# Schema_FoxDigi.net
KiCad netlist of a schematic drawn in EAGLE
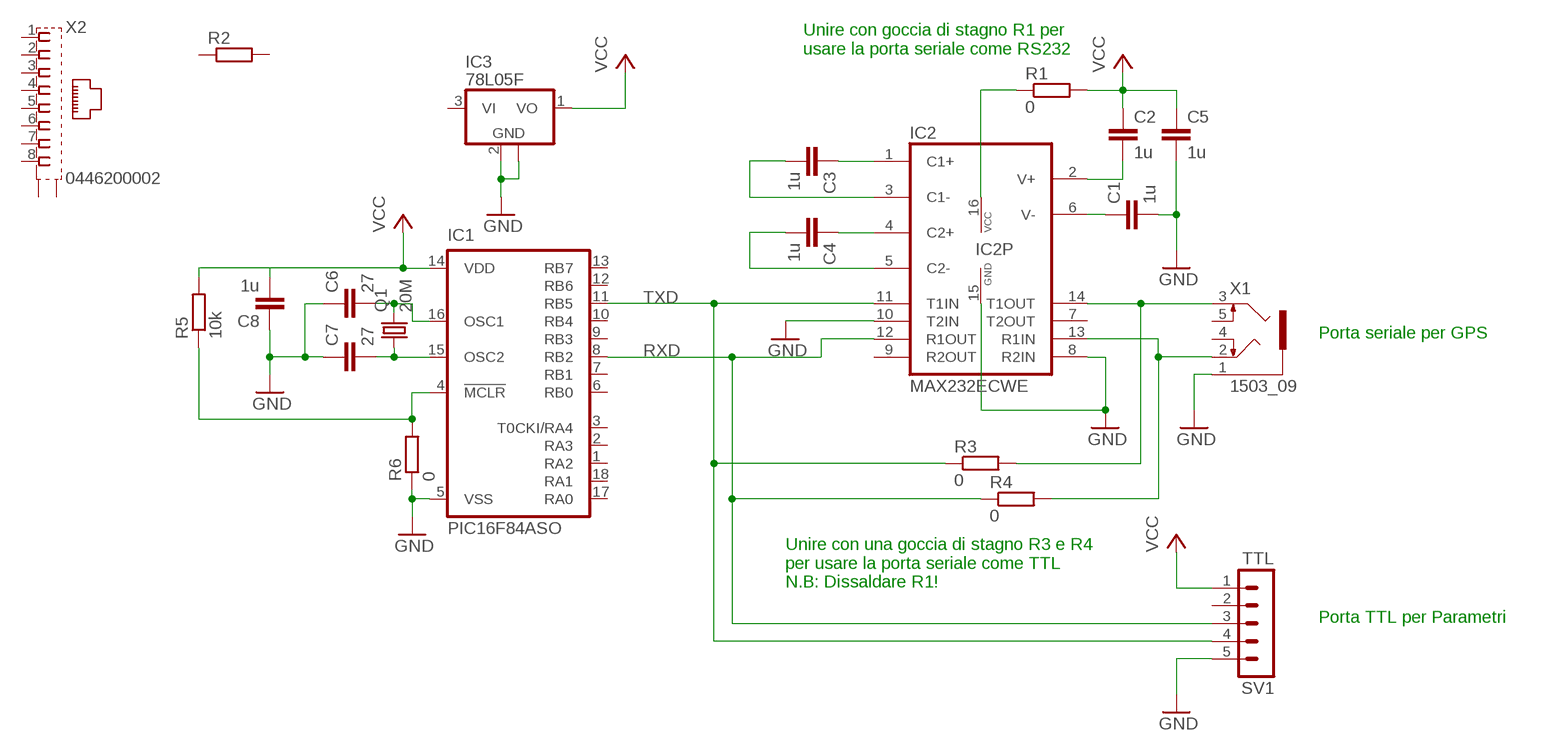
[diagram p0: schematic, sheet 1]

(export (version "E")
  (design (tool "Eeschema 10.0.6"))
  (components
    (comp (ref "C1")
      (value "1u")
      (footprint "eagle-import:C1206")
      (libsource (lib "eagle-import") (part "C-EUC1206"))
    )
    (comp (ref "C2")
      (value "1u")
      (footprint "eagle-import:C1206")
      (libsource (lib "eagle-import") (part "C-EUC1206"))
    )
    (comp (ref "C3")
      (value "1u")
      (footprint "eagle-import:C1206")
      (libsource (lib "eagle-import") (part "C-EUC1206"))
    )
    (comp (ref "C4")
      (value "1u")
      (footprint "eagle-import:C1206")
      (libsource (lib "eagle-import") (part "C-EUC1206"))
    )
    (comp (ref "C5")
      (value "1u")
      (footprint "eagle-import:C1206")
      (libsource (lib "eagle-import") (part "C-EUC1206"))
    )
    (comp (ref "C6")
      (value "27")
      (footprint "eagle-import:C025-025X050")
      (libsource (lib "eagle-import") (part "C-EU025-025X050"))
    )
    (comp (ref "C7")
      (value "27")
      (footprint "eagle-import:C025-025X050")
      (libsource (lib "eagle-import") (part "C-EU025-025X050"))
    )
    (comp (ref "C8")
      (value "1u")
      (footprint "eagle-import:C1206")
      (libsource (lib "eagle-import") (part "C-EUC1206"))
    )
    (comp (ref "IC1")
      (value "PIC16F84ASO")
      (footprint "eagle-import:SO-18W")
      (fields (field (name "MF") "MICROCHIP") (field (name "MPN") "PIC16F84A-04/SO"))
      (libsource (lib "eagle-import") (part "PIC16F8SO4A"))
    )
    (comp (ref "IC2")
      (value "MAX232ECWE")
      (footprint "eagle-import:SO16L")
      (fields (field (name "MF") "MAXIM") (field (name "MPN") "MAX232ECWE+"))
      (libsource (lib "eagle-import") (part "MAX232ECWE"))
    )
    (comp (ref "IC3")
      (value "78L05F")
      (footprint "eagle-import:SOT89")
      (libsource (lib "eagle-import") (part "78LF05"))
    )
    (comp (ref "Q1")
      (value "20M")
      (footprint "eagle-import:HC49_S")
      (libsource (lib "eagle-import") (part "CRYSTALHC49S"))
    )
    (comp (ref "R1")
      (value "0")
      (footprint "eagle-import:M1206")
      (libsource (lib "eagle-import") (part "R-EU_M1206"))
    )
    (comp (ref "R2")
      (value "R-EU_M1206")
      (footprint "eagle-import:M1206")
      (libsource (lib "eagle-import") (part "R-EU_M1206"))
    )
    (comp (ref "R3")
      (value "0")
      (footprint "eagle-import:M1206")
      (libsource (lib "eagle-import") (part "R-EU_M1206"))
    )
    (comp (ref "R4")
      (value "0")
      (footprint "eagle-import:M1206")
      (libsource (lib "eagle-import") (part "R-EU_M1206"))
    )
    (comp (ref "R5")
      (value "10k")
      (footprint "eagle-import:M1206")
      (libsource (lib "eagle-import") (part "R-EU_M1206"))
    )
    (comp (ref "R6")
      (value "0")
      (footprint "eagle-import:M1206")
      (libsource (lib "eagle-import") (part "R-EU_M1206"))
    )
    (comp (ref "SV1")
      (value "TTL")
      (footprint "eagle-import:MA05-1")
      (libsource (lib "eagle-import") (part "MA05-1"))
    )
    (comp (ref "X1")
      (value "1503_09")
      (footprint "eagle-import:1503_09")
      (libsource (lib "eagle-import") (part "1503_09"))
    )
    (comp (ref "X2")
      (value "0446200002")
      (footprint "eagle-import:0446200002")
      (fields (field (name "MF") "MOLEX"))
      (libsource (lib "eagle-import") (part "0446200002"))
    )
  )
  (nets
    (net (code "1") (name "/RXD") (class "Default")
      (node (ref "IC1") (pin "8") (pinfunction "RB2_8") (pintype "bidirectional"))
      (node (ref "IC2") (pin "12") (pinfunction "R1OUT_12") (pintype "output"))
      (node (ref "R4") (pin "1") (pinfunction "1_1") (pintype "passive"))
      (node (ref "SV1") (pin "3") (pinfunction "3_3") (pintype "passive"))
    )
    (net (code "2") (name "/TXD") (class "Default")
      (node (ref "IC1") (pin "11") (pinfunction "RB5_11") (pintype "bidirectional"))
      (node (ref "IC2") (pin "11") (pinfunction "T1IN_11") (pintype "input"))
      (node (ref "R3") (pin "1") (pinfunction "1_1") (pintype "passive"))
      (node (ref "SV1") (pin "4") (pinfunction "4_4") (pintype "passive"))
    )
    (net (code "3") (name "GND") (class "Default")
      (node (ref "C1") (pin "2") (pinfunction "2_2") (pintype "passive"))
      (node (ref "C5") (pin "2") (pinfunction "2_2") (pintype "passive"))
      (node (ref "C6") (pin "1") (pinfunction "1_1") (pintype "passive"))
      (node (ref "C7") (pin "1") (pinfunction "1_1") (pintype "passive"))
      (node (ref "C8") (pin "1") (pinfunction "1_1") (pintype "passive"))
      (node (ref "IC1") (pin "5") (pinfunction "VSS_5") (pintype "power_in"))
      (node (ref "IC2") (pin "10") (pinfunction "T2IN_10") (pintype "input"))
      (node (ref "IC2") (pin "15") (pinfunction "GND_15") (pintype "power_in"))
      (node (ref "IC2") (pin "8") (pinfunction "R2IN_8") (pintype "input"))
      (node (ref "IC3") (pin "2") (pinfunction "GND_2") (pintype "passive"))
      (node (ref "IC3") (pin "2@1") (pinfunction "GND_2@1") (pintype "passive"))
      (node (ref "R6") (pin "1") (pinfunction "1_1") (pintype "passive"))
      (node (ref "SV1") (pin "5") (pinfunction "5_5") (pintype "passive"))
      (node (ref "X1") (pin "1") (pinfunction "1_1") (pintype "passive"))
    )
    (net (code "4") (name "Net-(IC1-OSC1)") (class "Default")
      (node (ref "C6") (pin "2") (pinfunction "2_2") (pintype "passive"))
      (node (ref "IC1") (pin "16") (pinfunction "OSC1_16") (pintype "input"))
      (node (ref "Q1") (pin "2") (pinfunction "2_2") (pintype "passive"))
    )
    (net (code "5") (name "Net-(IC1-OSC2)") (class "Default")
      (node (ref "C7") (pin "2") (pinfunction "2_2") (pintype "passive"))
      (node (ref "IC1") (pin "15") (pinfunction "OSC2_15") (pintype "output"))
      (node (ref "Q1") (pin "1") (pinfunction "1_1") (pintype "passive"))
    )
    (net (code "6") (name "Net-(IC1-~{MCLR})") (class "Default")
      (node (ref "IC1") (pin "4") (pinfunction "~{MCLR}_4") (pintype "input"))
      (node (ref "R5") (pin "1") (pinfunction "1_1") (pintype "passive"))
      (node (ref "R6") (pin "2") (pinfunction "2_2") (pintype "passive"))
    )
    (net (code "7") (name "Net-(IC2A-C1+)") (class "Default")
      (node (ref "C3") (pin "1") (pinfunction "1_1") (pintype "passive"))
      (node (ref "IC2") (pin "1") (pinfunction "C1+_1") (pintype "bidirectional"))
    )
    (net (code "8") (name "Net-(IC2A-C1-)") (class "Default")
      (node (ref "C3") (pin "2") (pinfunction "2_2") (pintype "passive"))
      (node (ref "IC2") (pin "3") (pinfunction "C1-_3") (pintype "bidirectional"))
    )
    (net (code "9") (name "Net-(IC2A-C2+)") (class "Default")
      (node (ref "C4") (pin "1") (pinfunction "1_1") (pintype "passive"))
      (node (ref "IC2") (pin "4") (pinfunction "C2+_4") (pintype "bidirectional"))
    )
    (net (code "10") (name "Net-(IC2A-C2-)") (class "Default")
      (node (ref "C4") (pin "2") (pinfunction "2_2") (pintype "passive"))
      (node (ref "IC2") (pin "5") (pinfunction "C2-_5") (pintype "bidirectional"))
    )
    (net (code "11") (name "Net-(IC2A-R1IN)") (class "Default")
      (node (ref "IC2") (pin "13") (pinfunction "R1IN_13") (pintype "input"))
      (node (ref "R4") (pin "2") (pinfunction "2_2") (pintype "passive"))
      (node (ref "X1") (pin "2") (pinfunction "2_2") (pintype "passive"))
    )
    (net (code "12") (name "Net-(IC2A-T1OUT)") (class "Default")
      (node (ref "IC2") (pin "14") (pinfunction "T1OUT_14") (pintype "output"))
      (node (ref "R3") (pin "2") (pinfunction "2_2") (pintype "passive"))
      (node (ref "X1") (pin "3") (pinfunction "3_3") (pintype "passive"))
    )
    (net (code "13") (name "Net-(IC2A-V+)") (class "Default")
      (node (ref "C2") (pin "2") (pinfunction "2_2") (pintype "passive"))
      (node (ref "IC2") (pin "2") (pinfunction "V+_2") (pintype "bidirectional"))
    )
    (net (code "14") (name "Net-(IC2A-V-)") (class "Default")
      (node (ref "C1") (pin "1") (pinfunction "1_1") (pintype "passive"))
      (node (ref "IC2") (pin "6") (pinfunction "V-_6") (pintype "bidirectional"))
    )
    (net (code "15") (name "Net-(IC2B-VCC)") (class "Default")
      (node (ref "IC2") (pin "16") (pinfunction "VCC_16") (pintype "power_in"))
      (node (ref "R1") (pin "1") (pinfunction "1_1") (pintype "passive"))
    )
    (net (code "16") (name "VCC") (class "Default")
      (node (ref "C2") (pin "1") (pinfunction "1_1") (pintype "passive"))
      (node (ref "C5") (pin "1") (pinfunction "1_1") (pintype "passive"))
      (node (ref "C8") (pin "2") (pinfunction "2_2") (pintype "passive"))
      (node (ref "IC1") (pin "14") (pinfunction "VDD_14") (pintype "power_in"))
      (node (ref "IC3") (pin "1") (pinfunction "VO_1") (pintype "passive"))
      (node (ref "R1") (pin "2") (pinfunction "2_2") (pintype "passive"))
      (node (ref "R5") (pin "2") (pinfunction "2_2") (pintype "passive"))
      (node (ref "SV1") (pin "1") (pinfunction "1_1") (pintype "passive"))
    )
    (net (code "17") (name "unconnected-(IC1-RA0-Pad17)") (class "Default")
      (node (ref "IC1") (pin "17") (pinfunction "RA0_17") (pintype "bidirectional"))
    )
    (net (code "18") (name "unconnected-(IC1-RA1-Pad18)") (class "Default")
      (node (ref "IC1") (pin "18") (pinfunction "RA1_18") (pintype "bidirectional"))
    )
    (net (code "19") (name "unconnected-(IC1-RA2-Pad1)") (class "Default")
      (node (ref "IC1") (pin "1") (pinfunction "RA2_1") (pintype "bidirectional"))
    )
    (net (code "20") (name "unconnected-(IC1-RA3-Pad2)") (class "Default")
      (node (ref "IC1") (pin "2") (pinfunction "RA3_2") (pintype "bidirectional"))
    )
    (net (code "21") (name "unconnected-(IC1-RB0-Pad6)") (class "Default")
      (node (ref "IC1") (pin "6") (pinfunction "RB0_6") (pintype "bidirectional"))
    )
    (net (code "22") (name "unconnected-(IC1-RB1-Pad7)") (class "Default")
      (node (ref "IC1") (pin "7") (pinfunction "RB1_7") (pintype "bidirectional"))
    )
    (net (code "23") (name "unconnected-(IC1-RB3-Pad9)") (class "Default")
      (node (ref "IC1") (pin "9") (pinfunction "RB3_9") (pintype "bidirectional"))
    )
    (net (code "24") (name "unconnected-(IC1-RB4-Pad10)") (class "Default")
      (node (ref "IC1") (pin "10") (pinfunction "RB4_10") (pintype "bidirectional"))
    )
    (net (code "25") (name "unconnected-(IC1-RB6-Pad12)") (class "Default")
      (node (ref "IC1") (pin "12") (pinfunction "RB6_12") (pintype "bidirectional"))
    )
    (net (code "26") (name "unconnected-(IC1-RB7-Pad13)") (class "Default")
      (node (ref "IC1") (pin "13") (pinfunction "RB7_13") (pintype "bidirectional"))
    )
    (net (code "27") (name "unconnected-(IC1-T0CKI{slash}RA4-Pad3)") (class "Default")
      (node (ref "IC1") (pin "3") (pinfunction "T0CKI/RA4_3") (pintype "bidirectional"))
    )
    (net (code "28") (name "unconnected-(IC2A-R2OUT-Pad9)") (class "Default")
      (node (ref "IC2") (pin "9") (pinfunction "R2OUT_9") (pintype "output"))
    )
    (net (code "29") (name "unconnected-(IC2A-T2OUT-Pad7)") (class "Default")
      (node (ref "IC2") (pin "7") (pinfunction "T2OUT_7") (pintype "output"))
    )
    (net (code "30") (name "unconnected-(IC3-VI-Pad3)") (class "Default")
      (node (ref "IC3") (pin "3") (pinfunction "VI_3") (pintype "input"))
    )
    (net (code "31") (name "unconnected-(R2-Pad1)") (class "Default")
      (node (ref "R2") (pin "1") (pinfunction "1_1") (pintype "passive"))
    )
    (net (code "32") (name "unconnected-(R2-Pad2)") (class "Default")
      (node (ref "R2") (pin "2") (pinfunction "2_2") (pintype "passive"))
    )
    (net (code "33") (name "unconnected-(SV1-Pad2)") (class "Default")
      (node (ref "SV1") (pin "2") (pinfunction "2_2") (pintype "passive"))
    )
    (net (code "34") (name "unconnected-(X1-Pad4)") (class "Default")
      (node (ref "X1") (pin "4") (pinfunction "4_4") (pintype "passive"))
    )
    (net (code "35") (name "unconnected-(X1-Pad5)") (class "Default")
      (node (ref "X1") (pin "5") (pinfunction "5_5") (pintype "passive"))
    )
    (net (code "36") (name "unconnected-(X2-Pad1)") (class "Default")
      (node (ref "X2") (pin "1") (pinfunction "1_1") (pintype "passive"))
    )
    (net (code "37") (name "unconnected-(X2-Pad2)") (class "Default")
      (node (ref "X2") (pin "2") (pinfunction "2_2") (pintype "passive"))
    )
    (net (code "38") (name "unconnected-(X2-Pad3)") (class "Default")
      (node (ref "X2") (pin "3") (pinfunction "3_3") (pintype "passive"))
    )
    (net (code "39") (name "unconnected-(X2-Pad4)") (class "Default")
      (node (ref "X2") (pin "4") (pinfunction "4_4") (pintype "passive"))
    )
    (net (code "40") (name "unconnected-(X2-Pad5)") (class "Default")
      (node (ref "X2") (pin "5") (pinfunction "5_5") (pintype "passive"))
    )
    (net (code "41") (name "unconnected-(X2-Pad6)") (class "Default")
      (node (ref "X2") (pin "6") (pinfunction "6_6") (pintype "passive"))
    )
    (net (code "42") (name "unconnected-(X2-Pad7)") (class "Default")
      (node (ref "X2") (pin "7") (pinfunction "7_7") (pintype "passive"))
    )
    (net (code "43") (name "unconnected-(X2-Pad8)") (class "Default")
      (node (ref "X2") (pin "8") (pinfunction "8_8") (pintype "passive"))
    )
    (net (code "44") (name "unconnected-(X2-S1-PadS@1)") (class "Default")
      (node (ref "X2") (pin "S@1") (pinfunction "S1_S@1") (pintype "passive"))
    )
    (net (code "45") (name "unconnected-(X2-S2-PadS@2)") (class "Default")
      (node (ref "X2") (pin "S@2") (pinfunction "S2_S@2") (pintype "passive"))
    )
  )
)
